# ProProject_MPU6050__2024-06-20.net
KiCad netlist of a schematic drawn in EasyEDA Pro
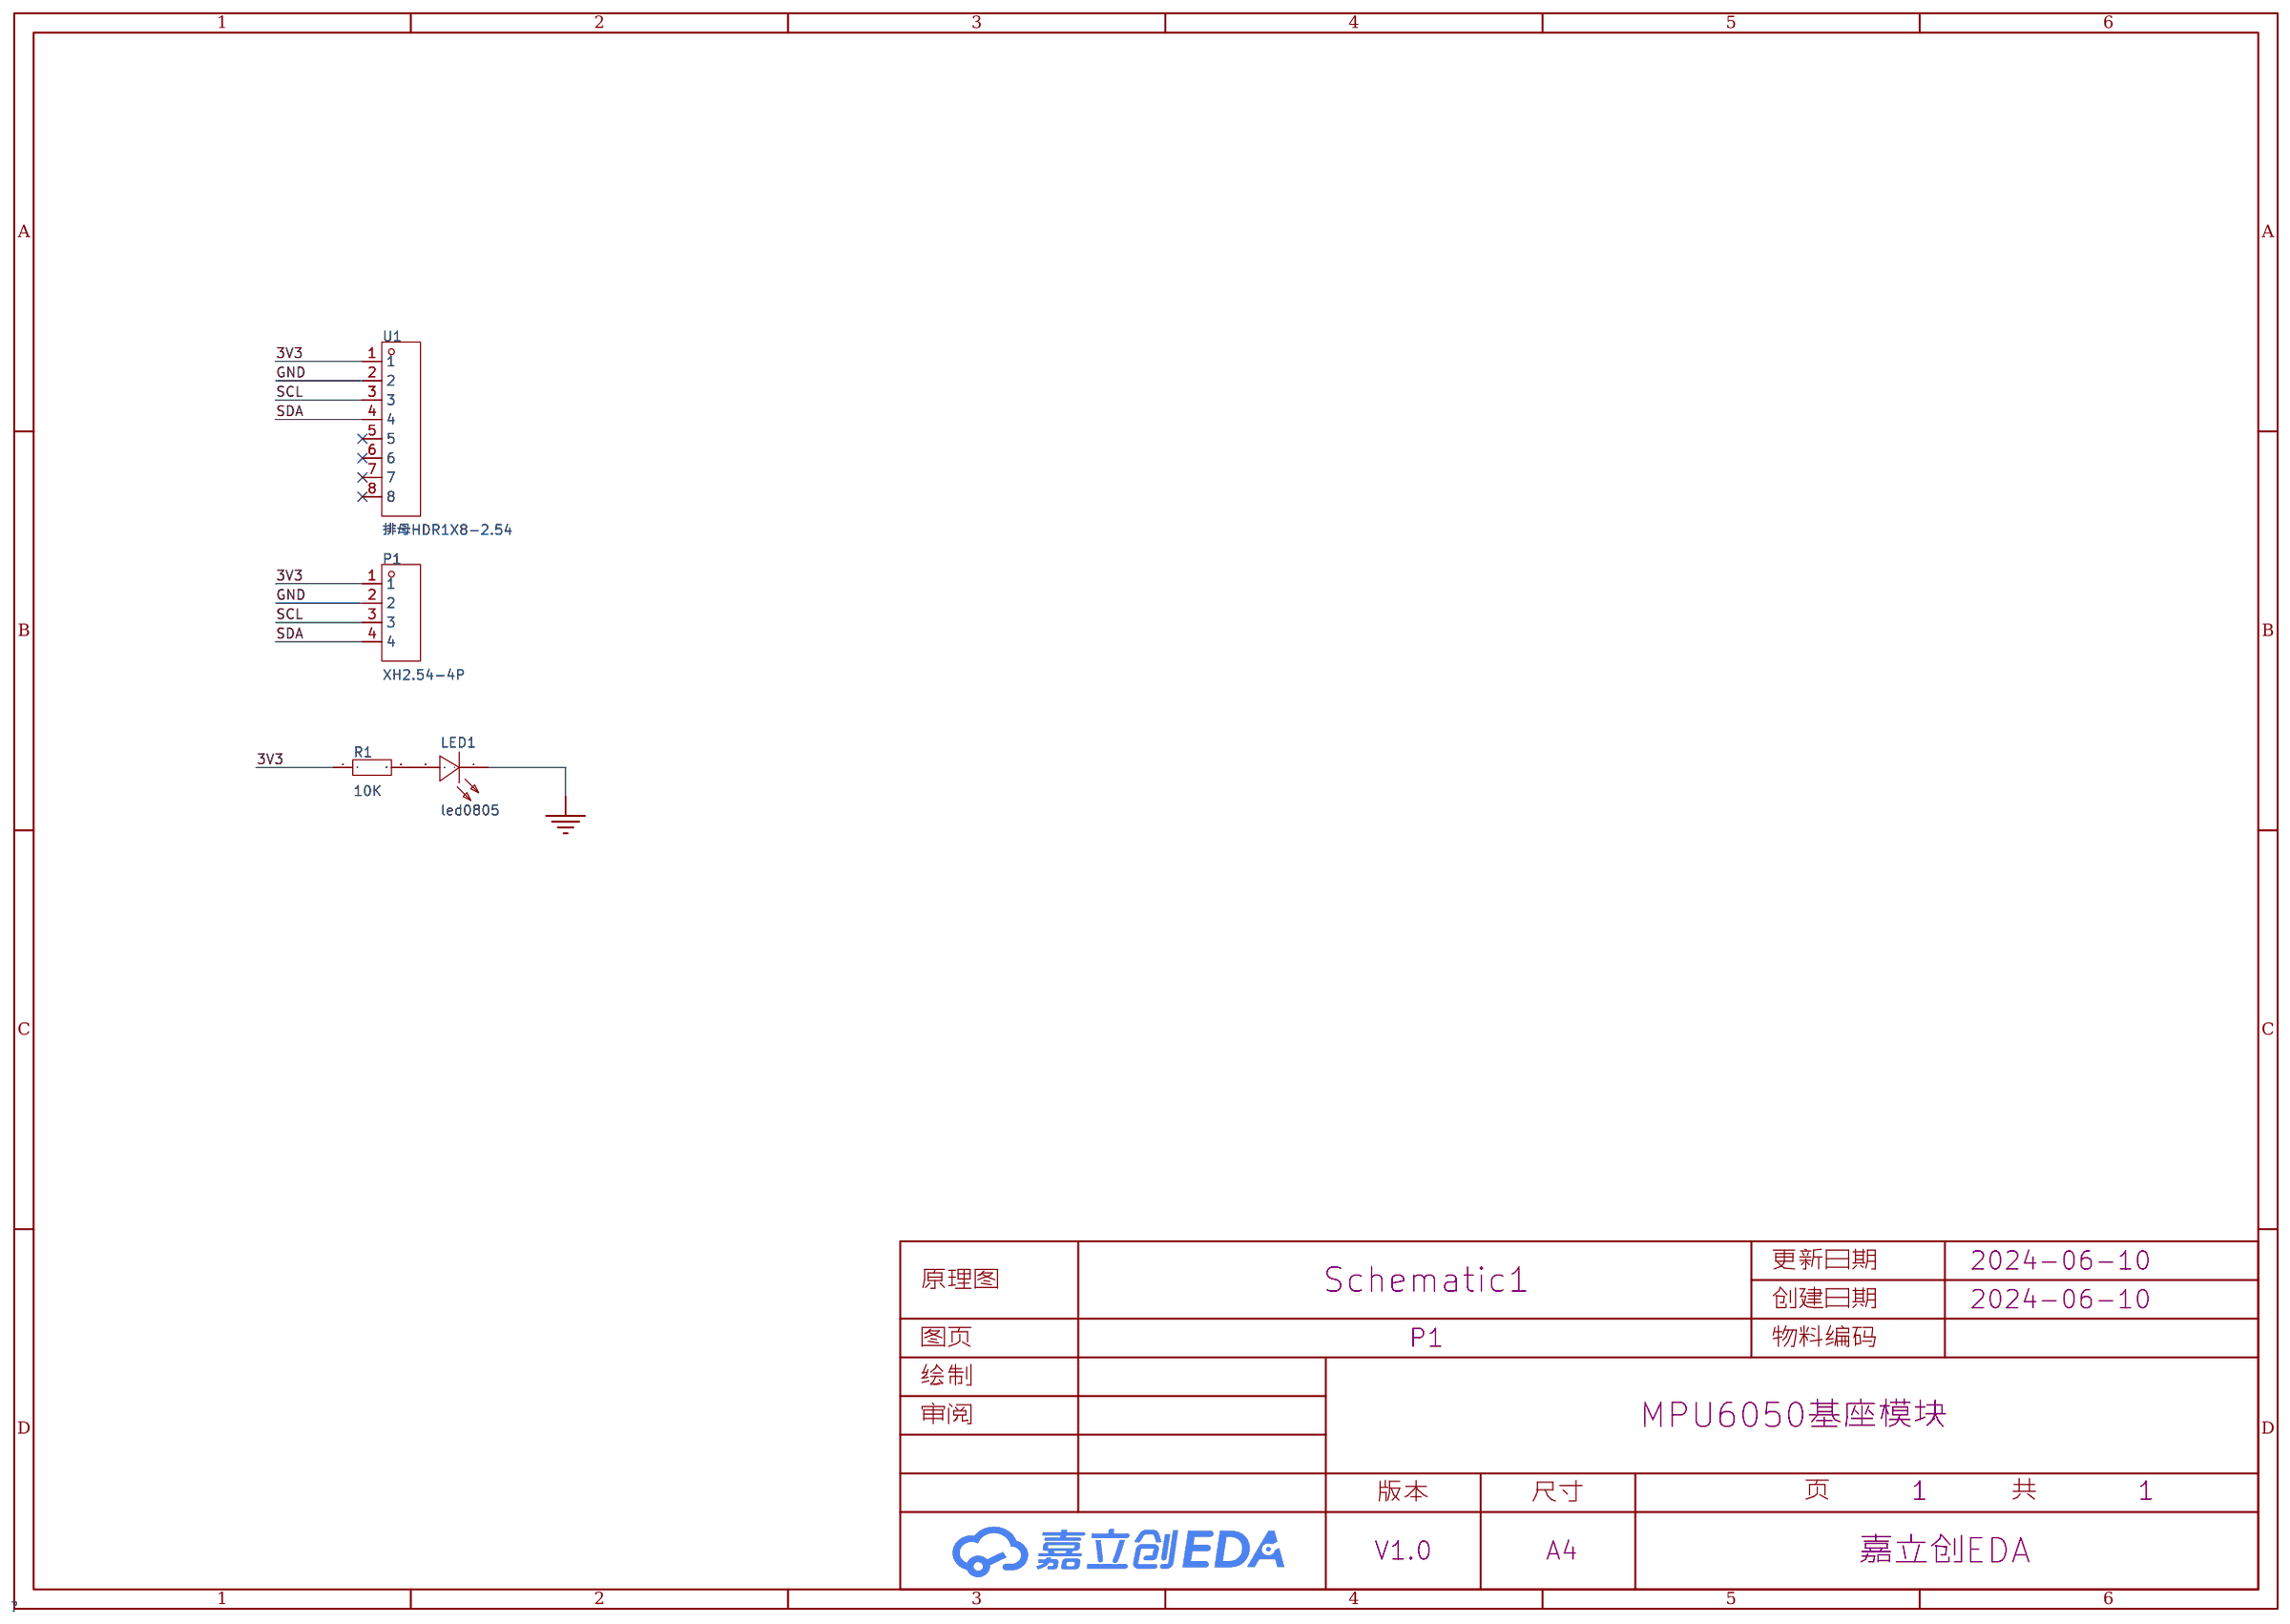
[diagram p0: schematic sheet]

(export (version "E")
  (design (tool "Eeschema 10.0.6"))
  (components
    (comp (ref "LED1")
      (value "led0805")
      (footprint "easyedapro:LED0805-RD")
      (libsource (lib "easyedapro") (part "LED0805"))
    )
    (comp (ref "P1")
      (value "XH2.54-4P")
      (footprint "easyedapro:CONN-TH_4P-P2.50-XH2.54-4P")
      (libsource (lib "easyedapro") (part "XH2.54-4P"))
    )
    (comp (ref "R1") (value "10K") (footprint "easyedapro:R0603") (libsource (lib "easyedapro") (part "电阻")))
    (comp (ref "U1")
      (value "排母HDR1X8-2.54")
      (footprint "easyedapro:HDR-TH_8P-P2.54-V-F")
      (libsource (lib "easyedapro") (part "排母HDR1X8-2.54"))
    )
  )
  (nets
    (net (code "1") (name "/3V3") (class "Default")
      (node (ref "P1") (pin "1") (pinfunction "1_1") (pintype "unspecified"))
      (node (ref "R1") (pin "1") (pinfunction "1_1") (pintype "input"))
      (node (ref "U1") (pin "1") (pinfunction "1_1") (pintype "unspecified"))
    )
    (net (code "2") (name "/SCL") (class "Default")
      (node (ref "P1") (pin "3") (pinfunction "3_3") (pintype "unspecified"))
      (node (ref "U1") (pin "3") (pinfunction "3_3") (pintype "unspecified"))
    )
    (net (code "3") (name "/SDA") (class "Default")
      (node (ref "P1") (pin "4") (pinfunction "4_4") (pintype "unspecified"))
      (node (ref "U1") (pin "4") (pinfunction "4_4") (pintype "unspecified"))
    )
    (net (code "4") (name "GND") (class "Default")
      (node (ref "LED1") (pin "1") (pinfunction "-_1") (pintype "unspecified"))
      (node (ref "P1") (pin "2") (pinfunction "2_2") (pintype "unspecified"))
      (node (ref "U1") (pin "2") (pinfunction "2_2") (pintype "unspecified"))
    )
    (net (code "5") (name "Net-(LED1-+)") (class "Default")
      (node (ref "LED1") (pin "2") (pinfunction "+_2") (pintype "unspecified"))
      (node (ref "R1") (pin "2") (pinfunction "2_2") (pintype "input"))
    )
    (net (code "6") (name "unconnected-(U1-Pad5)") (class "Default")
      (node (ref "U1") (pin "5") (pinfunction "5_5") (pintype "unspecified+no_connect"))
    )
    (net (code "7") (name "unconnected-(U1-Pad6)") (class "Default")
      (node (ref "U1") (pin "6") (pinfunction "6_6") (pintype "unspecified+no_connect"))
    )
    (net (code "8") (name "unconnected-(U1-Pad7)") (class "Default")
      (node (ref "U1") (pin "7") (pinfunction "7_7") (pintype "unspecified+no_connect"))
    )
    (net (code "9") (name "unconnected-(U1-Pad8)") (class "Default")
      (node (ref "U1") (pin "8") (pinfunction "8_8") (pintype "unspecified+no_connect"))
    )
  )
)
